# sensor_dsp.net
KiCad netlist of a schematic drawn in EAGLE
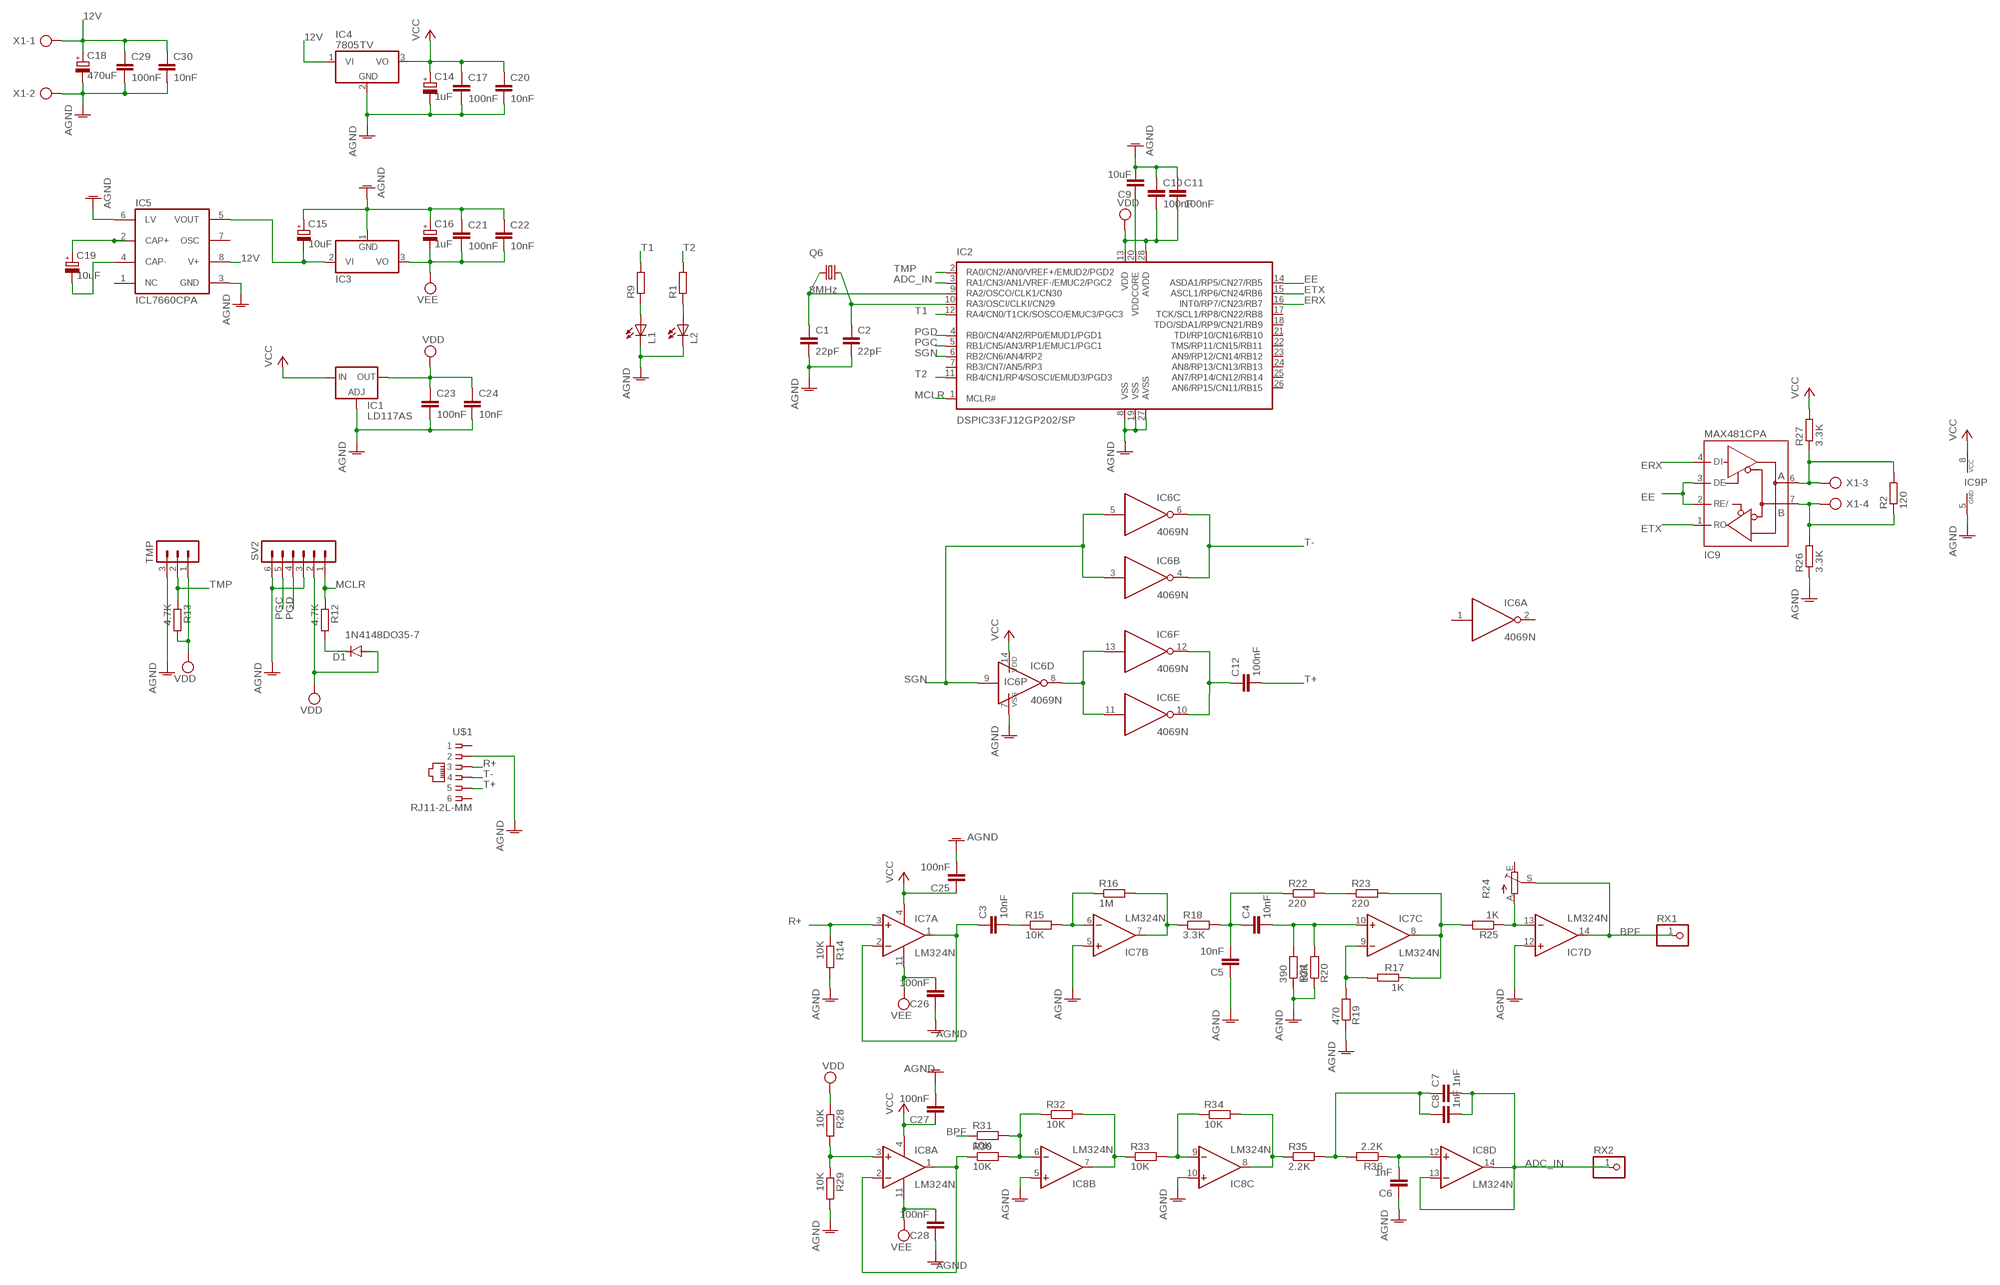
[diagram p0: schematic, sheet 1]

(export (version "E")
  (design (tool "Eeschema 10.0.6"))
  (components
    (comp (ref "C1")
      (value "22pF")
      (footprint "eagle-import:C025-024X044")
      (libsource (lib "eagle-import") (part "C-EU025-024X044"))
    )
    (comp (ref "C2")
      (value "22pF")
      (footprint "eagle-import:C025-024X044")
      (libsource (lib "eagle-import") (part "C-EU025-024X044"))
    )
    (comp (ref "C3")
      (value "10nF")
      (footprint "eagle-import:C5B2.5")
      (libsource (lib "eagle-import") (part "C5/2.5"))
    )
    (comp (ref "C4")
      (value "10nF")
      (footprint "eagle-import:C5B2.5")
      (libsource (lib "eagle-import") (part "C5/2.5"))
    )
    (comp (ref "C5")
      (value "10nF")
      (footprint "eagle-import:C5B2.5")
      (libsource (lib "eagle-import") (part "C5/2.5"))
    )
    (comp (ref "C6")
      (value "1nF")
      (footprint "eagle-import:C5B2.5")
      (libsource (lib "eagle-import") (part "C5/2.5"))
    )
    (comp (ref "C7")
      (value "1nF")
      (footprint "eagle-import:C5B2.5")
      (libsource (lib "eagle-import") (part "C5/2.5"))
    )
    (comp (ref "C8")
      (value "1nF")
      (footprint "eagle-import:C5B2.5")
      (libsource (lib "eagle-import") (part "C5/2.5"))
    )
    (comp (ref "C9")
      (value "10uF")
      (footprint "eagle-import:C050-024X044")
      (libsource (lib "eagle-import") (part "C-EU050-024X044"))
    )
    (comp (ref "C10")
      (value "100nF")
      (footprint "eagle-import:C5B2.5")
      (libsource (lib "eagle-import") (part "C5/2.5"))
    )
    (comp (ref "C11")
      (value "100nF")
      (footprint "eagle-import:C5B2.5")
      (libsource (lib "eagle-import") (part "C5/2.5"))
    )
    (comp (ref "C12")
      (value "100nF")
      (footprint "eagle-import:C5B2.5")
      (libsource (lib "eagle-import") (part "C5/2.5"))
    )
    (comp (ref "C14")
      (value "1uF")
      (footprint "eagle-import:E2,5-5")
      (libsource (lib "eagle-import") (part "CPOL-EUE2.5-5"))
    )
    (comp (ref "C15")
      (value "10uF")
      (footprint "eagle-import:E2,5-5")
      (libsource (lib "eagle-import") (part "CPOL-EUE2.5-5"))
    )
    (comp (ref "C16")
      (value "1uF")
      (footprint "eagle-import:E2,5-5")
      (libsource (lib "eagle-import") (part "CPOL-EUE2.5-5"))
    )
    (comp (ref "C17")
      (value "100nF")
      (footprint "eagle-import:C5B2.5")
      (libsource (lib "eagle-import") (part "C5/2.5"))
    )
    (comp (ref "C18")
      (value "470uF")
      (footprint "eagle-import:E3,5-8")
      (libsource (lib "eagle-import") (part "CPOL-EUE3.5-8"))
    )
    (comp (ref "C19")
      (value "10uF")
      (footprint "eagle-import:E2,5-5")
      (libsource (lib "eagle-import") (part "CPOL-EUE2.5-5"))
    )
    (comp (ref "C20")
      (value "10nF")
      (footprint "eagle-import:C5B2.5")
      (libsource (lib "eagle-import") (part "C5/2.5"))
    )
    (comp (ref "C21")
      (value "100nF")
      (footprint "eagle-import:C5B2.5")
      (libsource (lib "eagle-import") (part "C5/2.5"))
    )
    (comp (ref "C22")
      (value "10nF")
      (footprint "eagle-import:C5B2.5")
      (libsource (lib "eagle-import") (part "C5/2.5"))
    )
    (comp (ref "C23")
      (value "100nF")
      (footprint "eagle-import:C5B2.5")
      (libsource (lib "eagle-import") (part "C5/2.5"))
    )
    (comp (ref "C24")
      (value "10nF")
      (footprint "eagle-import:C5B2.5")
      (libsource (lib "eagle-import") (part "C5/2.5"))
    )
    (comp (ref "C25")
      (value "100nF")
      (footprint "eagle-import:C5B2.5")
      (libsource (lib "eagle-import") (part "C5/2.5"))
    )
    (comp (ref "C26")
      (value "100nF")
      (footprint "eagle-import:C5B2.5")
      (libsource (lib "eagle-import") (part "C5/2.5"))
    )
    (comp (ref "C27")
      (value "100nF")
      (footprint "eagle-import:C5B2.5")
      (libsource (lib "eagle-import") (part "C5/2.5"))
    )
    (comp (ref "C28")
      (value "100nF")
      (footprint "eagle-import:C5B2.5")
      (libsource (lib "eagle-import") (part "C5/2.5"))
    )
    (comp (ref "C29")
      (value "100nF")
      (footprint "eagle-import:C5B2.5")
      (libsource (lib "eagle-import") (part "C5/2.5"))
    )
    (comp (ref "C30")
      (value "10nF")
      (footprint "eagle-import:C5B2.5")
      (libsource (lib "eagle-import") (part "C5/2.5"))
    )
    (comp (ref "D1")
      (value "1N4148DO35-7")
      (footprint "eagle-import:DO35-7")
      (libsource (lib "eagle-import") (part "1N4148DO35-7"))
    )
    (comp (ref "IC1")
      (value "LD117AS")
      (footprint "eagle-import:SOT223")
      (libsource (lib "eagle-import") (part "LD117A?S12TR"))
    )
    (comp (ref "IC2")
      (value "DSPIC33FJ12GP202/SP")
      (footprint "eagle-import:DIL28-3")
      (libsource (lib "eagle-import") (part "DSPIC33FJ12GP202/SP"))
    )
    (comp (ref "IC3")
      (value "79")
      (footprint "eagle-import:TO220V")
      (libsource (lib "eagle-import") (part "79"))
    )
    (comp (ref "IC4")
      (value "7805TV")
      (footprint "eagle-import:TO220V")
      (libsource (lib "eagle-import") (part "78TV05"))
    )
    (comp (ref "IC5")
      (value "ICL7660CPA")
      (footprint "eagle-import:DIL08")
      (fields (field (name "MF") "INTERSIL"))
      (libsource (lib "eagle-import") (part "ICL7660CPA"))
    )
    (comp (ref "IC6")
      (value "4069N")
      (footprint "eagle-import:DIL14")
      (libsource (lib "eagle-import") (part "4069N"))
    )
    (comp (ref "IC7")
      (value "LM324N")
      (footprint "eagle-import:DIL14")
      (libsource (lib "eagle-import") (part "LM324N"))
    )
    (comp (ref "IC8")
      (value "LM324N")
      (footprint "eagle-import:DIL14")
      (libsource (lib "eagle-import") (part "LM324N"))
    )
    (comp (ref "IC9")
      (value "MAX481CPA")
      (footprint "eagle-import:DIL08")
      (fields (field (name "MPN") "MAX481CPA+"))
      (libsource (lib "eagle-import") (part "MAX481CPA"))
    )
    (comp (ref "L1")
      (value "LED3MM")
      (footprint "eagle-import:LED3MM")
      (libsource (lib "eagle-import") (part "LED3MM"))
    )
    (comp (ref "L2")
      (value "LED3MM")
      (footprint "eagle-import:LED3MM")
      (libsource (lib "eagle-import") (part "LED3MM"))
    )
    (comp (ref "Q6")
      (value "8MHz")
      (footprint "eagle-import:SM49")
      (libsource (lib "eagle-import") (part "CRYSTALSM49"))
    )
    (comp (ref "R1")
      (value "R-EU_0204/7")
      (footprint "eagle-import:0204_7")
      (libsource (lib "eagle-import") (part "rcl_334_R-EU_0204/7"))
    )
    (comp (ref "R2")
      (value "120")
      (footprint "eagle-import:0204_7")
      (libsource (lib "eagle-import") (part "rcl_334_R-EU_0204/7"))
    )
    (comp (ref "R9")
      (value "R-EU_0204/7")
      (footprint "eagle-import:0204_7")
      (libsource (lib "eagle-import") (part "rcl_334_R-EU_0204/7"))
    )
    (comp (ref "R12")
      (value "4.7K")
      (footprint "eagle-import:0204_7")
      (libsource (lib "eagle-import") (part "rcl_334_R-EU_0204/7"))
    )
    (comp (ref "R13")
      (value "4.7K")
      (footprint "eagle-import:0204_7")
      (libsource (lib "eagle-import") (part "rcl_334_R-EU_0204/7"))
    )
    (comp (ref "R14")
      (value "10K")
      (footprint "eagle-import:0204_7")
      (libsource (lib "eagle-import") (part "R-EU_0204/7"))
    )
    (comp (ref "R15")
      (value "10K")
      (footprint "eagle-import:0204_7")
      (libsource (lib "eagle-import") (part "rcl_334_R-EU_0204/7"))
    )
    (comp (ref "R16")
      (value "1M")
      (footprint "eagle-import:0204_7")
      (libsource (lib "eagle-import") (part "rcl_334_R-EU_0204/7"))
    )
    (comp (ref "R17")
      (value "1K")
      (footprint "eagle-import:0204_7")
      (libsource (lib "eagle-import") (part "rcl_334_R-EU_0204/7"))
    )
    (comp (ref "R18")
      (value "3.3K")
      (footprint "eagle-import:0204_7")
      (libsource (lib "eagle-import") (part "resistor_R-EU_0204/7"))
    )
    (comp (ref "R19")
      (value "470")
      (footprint "eagle-import:0204_7")
      (libsource (lib "eagle-import") (part "rcl_334_R-EU_0204/7"))
    )
    (comp (ref "R20")
      (value "10K")
      (footprint "eagle-import:0204_7")
      (libsource (lib "eagle-import") (part "rcl_334_R-EU_0204/7"))
    )
    (comp (ref "R21")
      (value "390")
      (footprint "eagle-import:0204_7")
      (libsource (lib "eagle-import") (part "rcl_334_R-EU_0204/7"))
    )
    (comp (ref "R22")
      (value "220")
      (footprint "eagle-import:0204_7")
      (libsource (lib "eagle-import") (part "rcl_334_R-EU_0204/7"))
    )
    (comp (ref "R23")
      (value "220")
      (footprint "eagle-import:0204_7")
      (libsource (lib "eagle-import") (part "rcl_334_R-EU_0204/7"))
    )
    (comp (ref "R24")
      (value "TRIM_EU-B64W")
      (footprint "eagle-import:B64W")
      (libsource (lib "eagle-import") (part "TRIM_EU-B64W"))
    )
    (comp (ref "R25")
      (value "1K")
      (footprint "eagle-import:0204_7")
      (libsource (lib "eagle-import") (part "rcl_334_R-EU_0204/7"))
    )
    (comp (ref "R26")
      (value "3.3K")
      (footprint "eagle-import:0204_7")
      (libsource (lib "eagle-import") (part "rcl_334_R-EU_0204/7"))
    )
    (comp (ref "R27")
      (value "3.3K")
      (footprint "eagle-import:0204_7")
      (libsource (lib "eagle-import") (part "rcl_334_R-EU_0204/7"))
    )
    (comp (ref "R28")
      (value "10K")
      (footprint "eagle-import:0204_7")
      (libsource (lib "eagle-import") (part "rcl_334_R-EU_0204/7"))
    )
    (comp (ref "R29")
      (value "10K")
      (footprint "eagle-import:0204_7")
      (libsource (lib "eagle-import") (part "rcl_334_R-EU_0204/7"))
    )
    (comp (ref "R30")
      (value "10K")
      (footprint "eagle-import:0204_7")
      (libsource (lib "eagle-import") (part "R-EU_0204/7"))
    )
    (comp (ref "R31")
      (value "10K")
      (footprint "eagle-import:0204_7")
      (libsource (lib "eagle-import") (part "rcl_334_R-EU_0204/7"))
    )
    (comp (ref "R32")
      (value "10K")
      (footprint "eagle-import:0204_7")
      (libsource (lib "eagle-import") (part "rcl_334_R-EU_0204/7"))
    )
    (comp (ref "R33")
      (value "10K")
      (footprint "eagle-import:0204_7")
      (libsource (lib "eagle-import") (part "rcl_334_R-EU_0204/7"))
    )
    (comp (ref "R34")
      (value "10K")
      (footprint "eagle-import:0204_7")
      (libsource (lib "eagle-import") (part "rcl_334_R-EU_0204/7"))
    )
    (comp (ref "R35")
      (value "2.2K")
      (footprint "eagle-import:0204_7")
      (libsource (lib "eagle-import") (part "rcl_334_R-EU_0204/7"))
    )
    (comp (ref "R36")
      (value "2.2K")
      (footprint "eagle-import:0204_7")
      (libsource (lib "eagle-import") (part "rcl_334_R-EU_0204/7"))
    )
    (comp (ref "RX1")
      (value "PINHD-1X1")
      (footprint "eagle-import:1X01")
      (libsource (lib "eagle-import") (part "PINHD-1X1"))
    )
    (comp (ref "RX2")
      (value "PINHD-1X1")
      (footprint "eagle-import:1X01")
      (libsource (lib "eagle-import") (part "PINHD-1X1"))
    )
    (comp (ref "SV2")
      (value "MA06-1")
      (footprint "eagle-import:MA06-1")
      (libsource (lib "eagle-import") (part "MA06-1"))
    )
    (comp (ref "TMP")
      (value "MA03-1")
      (footprint "eagle-import:MA03-1")
      (libsource (lib "eagle-import") (part "MA03-1"))
    )
    (comp (ref "U$1")
      (value "RJ11-2L-MM")
      (footprint "eagle-import:RJ11-NO_SHIELD_2")
      (libsource (lib "eagle-import") (part "RJ11-2L-MM"))
    )
    (comp (ref "X1")
      (value "AK300/4")
      (footprint "eagle-import:AK300_4")
      (libsource (lib "eagle-import") (part "AK300/4"))
    )
  )
  (nets
    (net (code "1") (name "/12V") (class "Default")
      (node (ref "C18") (pin "+") (pinfunction "+_+") (pintype "passive"))
      (node (ref "C29") (pin "1") (pinfunction "1_1") (pintype "passive"))
      (node (ref "C30") (pin "1") (pinfunction "1_1") (pintype "passive"))
      (node (ref "IC4") (pin "1") (pinfunction "VI_1") (pintype "input"))
      (node (ref "IC5") (pin "8") (pinfunction "V+_8") (pintype "power_in"))
      (node (ref "X1") (pin "1") (pinfunction "KL_1") (pintype "passive"))
    )
    (net (code "2") (name "/ADC_IN") (class "Default")
      (node (ref "C7") (pin "2") (pinfunction "2_2") (pintype "passive"))
      (node (ref "C8") (pin "2") (pinfunction "2_2") (pintype "passive"))
      (node (ref "IC2") (pin "3") (pinfunction "RA1/CN3/AN1/VREF-/EMUC2/PGC2_3") (pintype "bidirectional"))
      (node (ref "IC8") (pin "13") (pinfunction "-IN_13") (pintype "input"))
      (node (ref "IC8") (pin "14") (pinfunction "OUT_14") (pintype "output"))
      (node (ref "RX2") (pin "1") (pinfunction "1_1") (pintype "passive"))
    )
    (net (code "3") (name "/BPF") (class "Default")
      (node (ref "IC7") (pin "14") (pinfunction "OUT_14") (pintype "output"))
      (node (ref "R24") (pin "S") (pinfunction "S_S") (pintype "passive"))
      (node (ref "R31") (pin "1") (pinfunction "1_1") (pintype "passive"))
      (node (ref "RX1") (pin "1") (pinfunction "1_1") (pintype "passive"))
    )
    (net (code "4") (name "/EE") (class "Default")
      (node (ref "IC2") (pin "14") (pinfunction "ASDA1/RP5/CN27/RB5_14") (pintype "bidirectional"))
      (node (ref "IC9") (pin "2") (pinfunction "RE/_2") (pintype "input"))
      (node (ref "IC9") (pin "3") (pinfunction "DE_3") (pintype "input"))
    )
    (net (code "5") (name "/ERX") (class "Default")
      (node (ref "IC2") (pin "16") (pinfunction "INT0/RP7/CN23/RB7_16") (pintype "bidirectional"))
      (node (ref "IC9") (pin "4") (pinfunction "DI_4") (pintype "input"))
    )
    (net (code "6") (name "/ETX") (class "Default")
      (node (ref "IC2") (pin "15") (pinfunction "ASCL1/RP6/CN24/RB6_15") (pintype "bidirectional"))
      (node (ref "IC9") (pin "1") (pinfunction "RO_1") (pintype "output"))
    )
    (net (code "7") (name "/MCLR") (class "Default")
      (node (ref "IC2") (pin "1") (pinfunction "MCLR#_1") (pintype "input"))
      (node (ref "R12") (pin "1") (pinfunction "1_1") (pintype "passive"))
      (node (ref "SV2") (pin "1") (pinfunction "1_1") (pintype "passive"))
    )
    (net (code "8") (name "/PGC") (class "Default")
      (node (ref "IC2") (pin "5") (pinfunction "RB1/CN5/AN3/RP1/EMUC1/PGC1_5") (pintype "bidirectional"))
      (node (ref "SV2") (pin "5") (pinfunction "5_5") (pintype "passive"))
    )
    (net (code "9") (name "/PGD") (class "Default")
      (node (ref "IC2") (pin "4") (pinfunction "RB0/CN4/AN2/RP0/EMUD1/PGD1_4") (pintype "bidirectional"))
      (node (ref "SV2") (pin "4") (pinfunction "4_4") (pintype "passive"))
    )
    (net (code "10") (name "/R+") (class "Default")
      (node (ref "IC7") (pin "3") (pinfunction "+IN_3") (pintype "input"))
      (node (ref "R14") (pin "1") (pinfunction "1_1") (pintype "passive"))
      (node (ref "U$1") (pin "3") (pinfunction "3_3") (pintype "passive"))
    )
    (net (code "11") (name "/SGN") (class "Default")
      (node (ref "IC2") (pin "6") (pinfunction "RB2/CN6/AN4/RP2_6") (pintype "bidirectional"))
      (node (ref "IC6") (pin "3") (pinfunction "I_3") (pintype "input"))
      (node (ref "IC6") (pin "5") (pinfunction "I_5") (pintype "input"))
      (node (ref "IC6") (pin "9") (pinfunction "I_9") (pintype "input"))
    )
    (net (code "12") (name "/T+") (class "Default")
      (node (ref "C12") (pin "2") (pinfunction "2_2") (pintype "passive"))
      (node (ref "U$1") (pin "5") (pinfunction "5_5") (pintype "passive"))
    )
    (net (code "13") (name "/T-") (class "Default")
      (node (ref "IC6") (pin "4") (pinfunction "O_4") (pintype "output"))
      (node (ref "IC6") (pin "6") (pinfunction "O_6") (pintype "output"))
      (node (ref "U$1") (pin "4") (pinfunction "4_4") (pintype "passive"))
    )
    (net (code "14") (name "/T1") (class "Default")
      (node (ref "IC2") (pin "12") (pinfunction "RA4/CN0/T1CK/SOSCO/EMUC3/PGC3_12") (pintype "bidirectional"))
      (node (ref "R9") (pin "2") (pinfunction "2_2") (pintype "passive"))
    )
    (net (code "15") (name "/T2") (class "Default")
      (node (ref "IC2") (pin "11") (pinfunction "RB4/CN1/RP4/SOSCI/EMUD3/PGD3_11") (pintype "bidirectional"))
      (node (ref "R1") (pin "2") (pinfunction "2_2") (pintype "passive"))
    )
    (net (code "16") (name "/TMP") (class "Default")
      (node (ref "IC2") (pin "2") (pinfunction "RA0/CN2/AN0/VREF+/EMUD2/PGD2_2") (pintype "bidirectional"))
      (node (ref "R13") (pin "1") (pinfunction "1_1") (pintype "passive"))
      (node (ref "TMP") (pin "2") (pinfunction "2_2") (pintype "passive"))
    )
    (net (code "17") (name "AGND") (class "Default")
      (node (ref "C1") (pin "2") (pinfunction "2_2") (pintype "passive"))
      (node (ref "C10") (pin "1") (pinfunction "1_1") (pintype "passive"))
      (node (ref "C11") (pin "1") (pinfunction "1_1") (pintype "passive"))
      (node (ref "C14") (pin "-") (pinfunction "-_-") (pintype "passive"))
      (node (ref "C15") (pin "+") (pinfunction "+_+") (pintype "passive"))
      (node (ref "C16") (pin "+") (pinfunction "+_+") (pintype "passive"))
      (node (ref "C17") (pin "2") (pinfunction "2_2") (pintype "passive"))
      (node (ref "C18") (pin "-") (pinfunction "-_-") (pintype "passive"))
      (node (ref "C2") (pin "2") (pinfunction "2_2") (pintype "passive"))
      (node (ref "C20") (pin "2") (pinfunction "2_2") (pintype "passive"))
      (node (ref "C21") (pin "1") (pinfunction "1_1") (pintype "passive"))
      (node (ref "C22") (pin "1") (pinfunction "1_1") (pintype "passive"))
      (node (ref "C23") (pin "2") (pinfunction "2_2") (pintype "passive"))
      (node (ref "C24") (pin "2") (pinfunction "2_2") (pintype "passive"))
      (node (ref "C25") (pin "2") (pinfunction "2_2") (pintype "passive"))
      (node (ref "C26") (pin "1") (pinfunction "1_1") (pintype "passive"))
      (node (ref "C27") (pin "2") (pinfunction "2_2") (pintype "passive"))
      (node (ref "C28") (pin "1") (pinfunction "1_1") (pintype "passive"))
      (node (ref "C29") (pin "2") (pinfunction "2_2") (pintype "passive"))
      (node (ref "C30") (pin "2") (pinfunction "2_2") (pintype "passive"))
      (node (ref "C5") (pin "1") (pinfunction "1_1") (pintype "passive"))
      (node (ref "C6") (pin "1") (pinfunction "1_1") (pintype "passive"))
      (node (ref "C9") (pin "2") (pinfunction "2_2") (pintype "passive"))
      (node (ref "IC1") (pin "1") (pinfunction "ADJ_1") (pintype "input"))
      (node (ref "IC2") (pin "19") (pinfunction "VSS_19") (pintype "power_in"))
      (node (ref "IC2") (pin "27") (pinfunction "AVSS_27") (pintype "power_in"))
      (node (ref "IC2") (pin "8") (pinfunction "VSS_8") (pintype "power_in"))
      (node (ref "IC3") (pin "1") (pinfunction "GND_1") (pintype "passive"))
      (node (ref "IC4") (pin "2") (pinfunction "GND_2") (pintype "passive"))
      (node (ref "IC5") (pin "3") (pinfunction "GND_3") (pintype "power_in"))
      (node (ref "IC5") (pin "6") (pinfunction "LV_6") (pintype "passive"))
      (node (ref "IC6") (pin "7") (pinfunction "VSS_7") (pintype "power_in"))
      (node (ref "IC7") (pin "12") (pinfunction "+IN_12") (pintype "input"))
      (node (ref "IC7") (pin "5") (pinfunction "+IN_5") (pintype "input"))
      (node (ref "IC8") (pin "10") (pinfunction "+IN_10") (pintype "input"))
      (node (ref "IC8") (pin "5") (pinfunction "+IN_5") (pintype "input"))
      (node (ref "IC9") (pin "5") (pinfunction "GND_5") (pintype "power_in"))
      (node (ref "L1") (pin "K") (pinfunction "C_K") (pintype "passive"))
      (node (ref "L2") (pin "K") (pinfunction "C_K") (pintype "passive"))
      (node (ref "R14") (pin "2") (pinfunction "2_2") (pintype "passive"))
      (node (ref "R19") (pin "1") (pinfunction "1_1") (pintype "passive"))
      (node (ref "R20") (pin "1") (pinfunction "1_1") (pintype "passive"))
      (node (ref "R21") (pin "1") (pinfunction "1_1") (pintype "passive"))
      (node (ref "R26") (pin "1") (pinfunction "1_1") (pintype "passive"))
      (node (ref "R29") (pin "2") (pinfunction "2_2") (pintype "passive"))
      (node (ref "SV2") (pin "3") (pinfunction "3_3") (pintype "passive"))
      (node (ref "SV2") (pin "6") (pinfunction "6_6") (pintype "passive"))
      (node (ref "TMP") (pin "3") (pinfunction "3_3") (pintype "passive"))
      (node (ref "U$1") (pin "2") (pinfunction "2_2") (pintype "passive"))
      (node (ref "X1") (pin "2") (pinfunction "KL_2") (pintype "passive"))
    )
    (net (code "18") (name "Net-(C3-Pad2)") (class "Default")
      (node (ref "C3") (pin "2") (pinfunction "2_2") (pintype "passive"))
      (node (ref "R15") (pin "1") (pinfunction "1_1") (pintype "passive"))
    )
    (net (code "19") (name "Net-(C4-Pad1)") (class "Default")
      (node (ref "C4") (pin "1") (pinfunction "1_1") (pintype "passive"))
      (node (ref "C5") (pin "2") (pinfunction "2_2") (pintype "passive"))
      (node (ref "R18") (pin "2") (pinfunction "2_2") (pintype "passive"))
      (node (ref "R22") (pin "1") (pinfunction "1_1") (pintype "passive"))
    )
    (net (code "20") (name "Net-(C7-Pad1)") (class "Default")
      (node (ref "C7") (pin "1") (pinfunction "1_1") (pintype "passive"))
      (node (ref "C8") (pin "1") (pinfunction "1_1") (pintype "passive"))
      (node (ref "R35") (pin "2") (pinfunction "2_2") (pintype "passive"))
      (node (ref "R36") (pin "2") (pinfunction "2_2") (pintype "passive"))
    )
    (net (code "21") (name "Net-(D1-PadC)") (class "Default")
      (node (ref "D1") (pin "C") (pinfunction "C_C") (pintype "passive"))
      (node (ref "R12") (pin "2") (pinfunction "2_2") (pintype "passive"))
    )
    (net (code "22") (name "Net-(IC2-RA2{slash}OSCO{slash}CLK1{slash}CN30)") (class "Default")
      (node (ref "C1") (pin "1") (pinfunction "1_1") (pintype "passive"))
      (node (ref "IC2") (pin "9") (pinfunction "RA2/OSCO/CLK1/CN30_9") (pintype "bidirectional"))
      (node (ref "Q6") (pin "1") (pinfunction "1_1") (pintype "passive"))
    )
    (net (code "23") (name "Net-(IC2-RA3{slash}OSCI{slash}CLKI{slash}CN29)") (class "Default")
      (node (ref "C2") (pin "1") (pinfunction "1_1") (pintype "passive"))
      (node (ref "IC2") (pin "10") (pinfunction "RA3/OSCI/CLKI/CN29_10") (pintype "bidirectional"))
      (node (ref "Q6") (pin "2") (pinfunction "2_2") (pintype "passive"))
    )
    (net (code "24") (name "Net-(IC2-VDDCORE)") (class "Default")
      (node (ref "C9") (pin "1") (pinfunction "1_1") (pintype "passive"))
      (node (ref "IC2") (pin "20") (pinfunction "VDDCORE_20") (pintype "power_in"))
    )
    (net (code "25") (name "Net-(IC3-VI)") (class "Default")
      (node (ref "C15") (pin "-") (pinfunction "-_-") (pintype "passive"))
      (node (ref "IC3") (pin "2") (pinfunction "VI_2") (pintype "input"))
      (node (ref "IC5") (pin "5") (pinfunction "VOUT_5") (pintype "output"))
    )
    (net (code "26") (name "Net-(IC5-CAP+)") (class "Default")
      (node (ref "C19") (pin "+") (pinfunction "+_+") (pintype "passive"))
      (node (ref "IC5") (pin "2") (pinfunction "CAP+_2") (pintype "passive"))
    )
    (net (code "27") (name "Net-(IC5-CAP-)") (class "Default")
      (node (ref "C19") (pin "-") (pinfunction "-_-") (pintype "passive"))
      (node (ref "IC5") (pin "4") (pinfunction "CAP-_4") (pintype "passive"))
    )
    (net (code "28") (name "Net-(IC6D-O)") (class "Default")
      (node (ref "IC6") (pin "11") (pinfunction "I_11") (pintype "input"))
      (node (ref "IC6") (pin "13") (pinfunction "I_13") (pintype "input"))
      (node (ref "IC6") (pin "8") (pinfunction "O_8") (pintype "output"))
    )
    (net (code "29") (name "Net-(IC6E-O)") (class "Default")
      (node (ref "C12") (pin "1") (pinfunction "1_1") (pintype "passive"))
      (node (ref "IC6") (pin "10") (pinfunction "O_10") (pintype "output"))
      (node (ref "IC6") (pin "12") (pinfunction "O_12") (pintype "output"))
    )
    (net (code "30") (name "Net-(IC7A--IN)") (class "Default")
      (node (ref "C3") (pin "1") (pinfunction "1_1") (pintype "passive"))
      (node (ref "IC7") (pin "1") (pinfunction "OUT_1") (pintype "output"))
      (node (ref "IC7") (pin "2") (pinfunction "-IN_2") (pintype "input"))
    )
    (net (code "31") (name "Net-(IC7B--IN)") (class "Default")
      (node (ref "IC7") (pin "6") (pinfunction "-IN_6") (pintype "input"))
      (node (ref "R15") (pin "2") (pinfunction "2_2") (pintype "passive"))
      (node (ref "R16") (pin "1") (pinfunction "1_1") (pintype "passive"))
    )
    (net (code "32") (name "Net-(IC7B-OUT)") (class "Default")
      (node (ref "IC7") (pin "7") (pinfunction "OUT_7") (pintype "output"))
      (node (ref "R16") (pin "2") (pinfunction "2_2") (pintype "passive"))
      (node (ref "R18") (pin "1") (pinfunction "1_1") (pintype "passive"))
    )
    (net (code "33") (name "Net-(IC7C-+IN)") (class "Default")
      (node (ref "C4") (pin "2") (pinfunction "2_2") (pintype "passive"))
      (node (ref "IC7") (pin "10") (pinfunction "+IN_10") (pintype "input"))
      (node (ref "R20") (pin "2") (pinfunction "2_2") (pintype "passive"))
      (node (ref "R21") (pin "2") (pinfunction "2_2") (pintype "passive"))
    )
    (net (code "34") (name "Net-(IC7C--IN)") (class "Default")
      (node (ref "IC7") (pin "9") (pinfunction "-IN_9") (pintype "input"))
      (node (ref "R17") (pin "2") (pinfunction "2_2") (pintype "passive"))
      (node (ref "R19") (pin "2") (pinfunction "2_2") (pintype "passive"))
    )
    (net (code "35") (name "Net-(IC7C-OUT)") (class "Default")
      (node (ref "IC7") (pin "8") (pinfunction "OUT_8") (pintype "output"))
      (node (ref "R17") (pin "1") (pinfunction "1_1") (pintype "passive"))
      (node (ref "R23") (pin "2") (pinfunction "2_2") (pintype "passive"))
      (node (ref "R25") (pin "2") (pinfunction "2_2") (pintype "passive"))
    )
    (net (code "36") (name "Net-(IC7D--IN)") (class "Default")
      (node (ref "IC7") (pin "13") (pinfunction "-IN_13") (pintype "input"))
      (node (ref "R24") (pin "A") (pinfunction "A_A") (pintype "passive"))
      (node (ref "R25") (pin "1") (pinfunction "1_1") (pintype "passive"))
    )
    (net (code "37") (name "Net-(IC8A-+IN)") (class "Default")
      (node (ref "IC8") (pin "3") (pinfunction "+IN_3") (pintype "input"))
      (node (ref "R28") (pin "2") (pinfunction "2_2") (pintype "passive"))
      (node (ref "R29") (pin "1") (pinfunction "1_1") (pintype "passive"))
    )
    (net (code "38") (name "Net-(IC8A--IN)") (class "Default")
      (node (ref "IC8") (pin "1") (pinfunction "OUT_1") (pintype "output"))
      (node (ref "IC8") (pin "2") (pinfunction "-IN_2") (pintype "input"))
      (node (ref "R30") (pin "1") (pinfunction "1_1") (pintype "passive"))
    )
    (net (code "39") (name "Net-(IC8B--IN)") (class "Default")
      (node (ref "IC8") (pin "6") (pinfunction "-IN_6") (pintype "input"))
      (node (ref "R30") (pin "2") (pinfunction "2_2") (pintype "passive"))
      (node (ref "R31") (pin "2") (pinfunction "2_2") (pintype "passive"))
      (node (ref "R32") (pin "1") (pinfunction "1_1") (pintype "passive"))
    )
    (net (code "40") (name "Net-(IC8B-OUT)") (class "Default")
      (node (ref "IC8") (pin "7") (pinfunction "OUT_7") (pintype "output"))
      (node (ref "R32") (pin "2") (pinfunction "2_2") (pintype "passive"))
      (node (ref "R33") (pin "1") (pinfunction "1_1") (pintype "passive"))
    )
    (net (code "41") (name "Net-(IC8C--IN)") (class "Default")
      (node (ref "IC8") (pin "9") (pinfunction "-IN_9") (pintype "input"))
      (node (ref "R33") (pin "2") (pinfunction "2_2") (pintype "passive"))
      (node (ref "R34") (pin "1") (pinfunction "1_1") (pintype "passive"))
    )
    (net (code "42") (name "Net-(IC8C-OUT)") (class "Default")
      (node (ref "IC8") (pin "8") (pinfunction "OUT_8") (pintype "output"))
      (node (ref "R34") (pin "2") (pinfunction "2_2") (pintype "passive"))
      (node (ref "R35") (pin "1") (pinfunction "1_1") (pintype "passive"))
    )
    (net (code "43") (name "Net-(IC8D-+IN)") (class "Default")
      (node (ref "C6") (pin "2") (pinfunction "2_2") (pintype "passive"))
      (node (ref "IC8") (pin "12") (pinfunction "+IN_12") (pintype "input"))
      (node (ref "R36") (pin "1") (pinfunction "1_1") (pintype "passive"))
    )
    (net (code "44") (name "Net-(IC9A-A)") (class "Default")
      (node (ref "IC9") (pin "6") (pinfunction "A_6") (pintype "passive"))
      (node (ref "R2") (pin "2") (pinfunction "2_2") (pintype "passive"))
      (node (ref "R27") (pin "1") (pinfunction "1_1") (pintype "passive"))
      (node (ref "X1") (pin "3") (pinfunction "KL_3") (pintype "passive"))
    )
    (net (code "45") (name "Net-(IC9A-B)") (class "Default")
      (node (ref "IC9") (pin "7") (pinfunction "B_7") (pintype "passive"))
      (node (ref "R2") (pin "1") (pinfunction "1_1") (pintype "passive"))
      (node (ref "R26") (pin "2") (pinfunction "2_2") (pintype "passive"))
      (node (ref "X1") (pin "4") (pinfunction "KL_4") (pintype "passive"))
    )
    (net (code "46") (name "Net-(L1-PadA)") (class "Default")
      (node (ref "L1") (pin "A") (pinfunction "A_A") (pintype "passive"))
      (node (ref "R9") (pin "1") (pinfunction "1_1") (pintype "passive"))
    )
    (net (code "47") (name "Net-(L2-PadA)") (class "Default")
      (node (ref "L2") (pin "A") (pinfunction "A_A") (pintype "passive"))
      (node (ref "R1") (pin "1") (pinfunction "1_1") (pintype "passive"))
    )
    (net (code "48") (name "Net-(R22-Pad2)") (class "Default")
      (node (ref "R22") (pin "2") (pinfunction "2_2") (pintype "passive"))
      (node (ref "R23") (pin "1") (pinfunction "1_1") (pintype "passive"))
    )
    (net (code "49") (name "VCC") (class "Default")
      (node (ref "C14") (pin "+") (pinfunction "+_+") (pintype "passive"))
      (node (ref "C17") (pin "1") (pinfunction "1_1") (pintype "passive"))
      (node (ref "C20") (pin "1") (pinfunction "1_1") (pintype "passive"))
      (node (ref "C25") (pin "1") (pinfunction "1_1") (pintype "passive"))
      (node (ref "C27") (pin "1") (pinfunction "1_1") (pintype "passive"))
      (node (ref "IC1") (pin "3") (pinfunction "IN_3") (pintype "input"))
      (node (ref "IC4") (pin "3") (pinfunction "VO_3") (pintype "passive"))
      (node (ref "IC6") (pin "14") (pinfunction "VDD_14") (pintype "power_in"))
      (node (ref "IC7") (pin "4") (pinfunction "V+_4") (pintype "power_in"))
      (node (ref "IC8") (pin "4") (pinfunction "V+_4") (pintype "power_in"))
      (node (ref "IC9") (pin "8") (pinfunction "VCC_8") (pintype "power_in"))
      (node (ref "R27") (pin "2") (pinfunction "2_2") (pintype "passive"))
    )
    (net (code "50") (name "VDD") (class "Default")
      (node (ref "C10") (pin "2") (pinfunction "2_2") (pintype "passive"))
      (node (ref "C11") (pin "2") (pinfunction "2_2") (pintype "passive"))
      (node (ref "C23") (pin "1") (pinfunction "1_1") (pintype "passive"))
      (node (ref "C24") (pin "1") (pinfunction "1_1") (pintype "passive"))
      (node (ref "D1") (pin "A") (pinfunction "A_A") (pintype "passive"))
      (node (ref "IC1") (pin "4") (pinfunction "OUT_4") (pintype "passive"))
      (node (ref "IC2") (pin "13") (pinfunction "VDD_13") (pintype "power_in"))
      (node (ref "IC2") (pin "28") (pinfunction "AVDD_28") (pintype "power_in"))
      (node (ref "R13") (pin "2") (pinfunction "2_2") (pintype "passive"))
      (node (ref "R28") (pin "1") (pinfunction "1_1") (pintype "passive"))
      (node (ref "SV2") (pin "2") (pinfunction "2_2") (pintype "passive"))
      (node (ref "TMP") (pin "1") (pinfunction "1_1") (pintype "passive"))
    )
    (net (code "51") (name "VEE") (class "Default")
      (node (ref "C16") (pin "-") (pinfunction "-_-") (pintype "passive"))
      (node (ref "C21") (pin "2") (pinfunction "2_2") (pintype "passive"))
      (node (ref "C22") (pin "2") (pinfunction "2_2") (pintype "passive"))
      (node (ref "C26") (pin "2") (pinfunction "2_2") (pintype "passive"))
      (node (ref "C28") (pin "2") (pinfunction "2_2") (pintype "passive"))
      (node (ref "IC3") (pin "3") (pinfunction "VO_3") (pintype "passive"))
      (node (ref "IC7") (pin "11") (pinfunction "V-_11") (pintype "power_in"))
      (node (ref "IC8") (pin "11") (pinfunction "V-_11") (pintype "power_in"))
    )
    (net (code "52") (name "unconnected-(IC2-AN6{slash}RP15{slash}CN11{slash}RB15-Pad26)") (class "Default")
      (node (ref "IC2") (pin "26") (pinfunction "AN6/RP15/CN11/RB15_26") (pintype "bidirectional"))
    )
    (net (code "53") (name "unconnected-(IC2-AN7{slash}RP14{slash}CN12{slash}RB14-Pad25)") (class "Default")
      (node (ref "IC2") (pin "25") (pinfunction "AN7/RP14/CN12/RB14_25") (pintype "bidirectional"))
    )
    (net (code "54") (name "unconnected-(IC2-AN8{slash}RP13{slash}CN13{slash}RB13-Pad24)") (class "Default")
      (node (ref "IC2") (pin "24") (pinfunction "AN8/RP13/CN13/RB13_24") (pintype "bidirectional"))
    )
    (net (code "55") (name "unconnected-(IC2-AN9{slash}RP12{slash}CN14{slash}RB12-Pad23)") (class "Default")
      (node (ref "IC2") (pin "23") (pinfunction "AN9/RP12/CN14/RB12_23") (pintype "bidirectional"))
    )
    (net (code "56") (name "unconnected-(IC2-RB3{slash}CN7{slash}AN5{slash}RP3-Pad7)") (class "Default")
      (node (ref "IC2") (pin "7") (pinfunction "RB3/CN7/AN5/RP3_7") (pintype "bidirectional"))
    )
    (net (code "57") (name "unconnected-(IC2-TCK{slash}SCL1{slash}RP8{slash}CN22{slash}RB8-Pad17)") (class "Default")
      (node (ref "IC2") (pin "17") (pinfunction "TCK/SCL1/RP8/CN22/RB8_17") (pintype "bidirectional"))
    )
    (net (code "58") (name "unconnected-(IC2-TDI{slash}RP10{slash}CN16{slash}RB10-Pad21)") (class "Default")
      (node (ref "IC2") (pin "21") (pinfunction "TDI/RP10/CN16/RB10_21") (pintype "bidirectional"))
    )
    (net (code "59") (name "unconnected-(IC2-TDO{slash}SDA1{slash}RP9{slash}CN21{slash}RB9-Pad18)") (class "Default")
      (node (ref "IC2") (pin "18") (pinfunction "TDO/SDA1/RP9/CN21/RB9_18") (pintype "bidirectional"))
    )
    (net (code "60") (name "unconnected-(IC2-TMS{slash}RP11{slash}CN15{slash}RB11-Pad22)") (class "Default")
      (node (ref "IC2") (pin "22") (pinfunction "TMS/RP11/CN15/RB11_22") (pintype "bidirectional"))
    )
    (net (code "61") (name "unconnected-(IC5-NC-Pad1)") (class "Default")
      (node (ref "IC5") (pin "1") (pinfunction "NC_1") (pintype "no_connect"))
    )
    (net (code "62") (name "unconnected-(IC5-OSC-Pad7)") (class "Default")
      (node (ref "IC5") (pin "7") (pinfunction "OSC_7") (pintype "output"))
    )
    (net (code "63") (name "unconnected-(IC6A-I-Pad1)") (class "Default")
      (node (ref "IC6") (pin "1") (pinfunction "I_1") (pintype "input"))
    )
    (net (code "64") (name "unconnected-(IC6A-O-Pad2)") (class "Default")
      (node (ref "IC6") (pin "2") (pinfunction "O_2") (pintype "output"))
    )
    (net (code "65") (name "unconnected-(R24-PadE)") (class "Default")
      (node (ref "R24") (pin "E") (pinfunction "E_E") (pintype "passive"))
    )
    (net (code "66") (name "unconnected-(U$1-Pad1)") (class "Default")
      (node (ref "U$1") (pin "1") (pinfunction "1_1") (pintype "passive"))
    )
    (net (code "67") (name "unconnected-(U$1-Pad6)") (class "Default")
      (node (ref "U$1") (pin "6") (pinfunction "6_6") (pintype "passive"))
    )
  )
)
